# Sheet1.net
KiCad netlist of a schematic drawn in Altium Designer
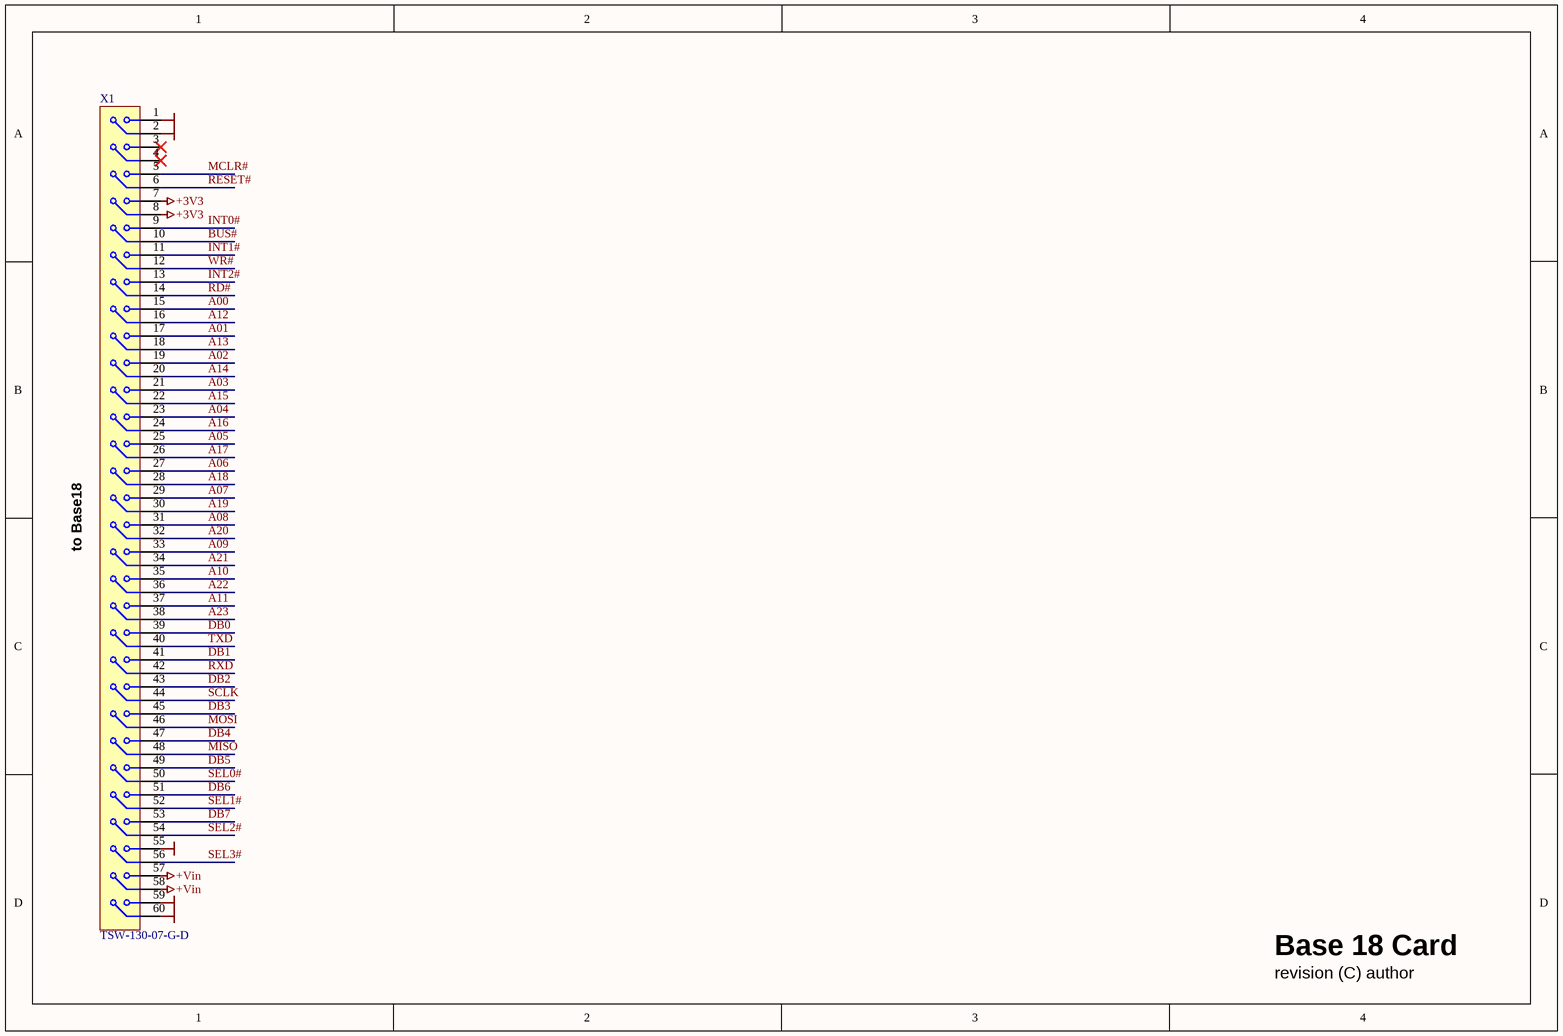
[diagram p0: Sheet1.SchDoc]

(export (version "E")
  (design (tool "Eeschema 10.0.6"))
  (components
    (comp (ref "X1")
      (value "TSW-130-07-G-D")
      (footprint "DIL60-M-EDGE")
      (description "Dual row, 60-way connector")
      (libsource (lib "Connectors") (part "Connector 2x30"))
    )
  )
  (nets
    (net (code "1") (name "+3V3") (class "Default")
      (node (ref "X1") (pin "7") (pinfunction "7_7") (pintype "passive"))
      (node (ref "X1") (pin "8") (pinfunction "8_8") (pintype "passive"))
    )
    (net (code "2") (name "+Vin") (class "Default")
      (node (ref "X1") (pin "57") (pinfunction "57_57") (pintype "passive"))
      (node (ref "X1") (pin "58") (pinfunction "58_58") (pintype "passive"))
    )
    (net (code "3") (name "/A00") (class "Default")
      (node (ref "X1") (pin "15") (pinfunction "15_15") (pintype "passive"))
    )
    (net (code "4") (name "/A01") (class "Default")
      (node (ref "X1") (pin "17") (pinfunction "17_17") (pintype "passive"))
    )
    (net (code "5") (name "/A02") (class "Default")
      (node (ref "X1") (pin "19") (pinfunction "19_19") (pintype "passive"))
    )
    (net (code "6") (name "/A03") (class "Default")
      (node (ref "X1") (pin "21") (pinfunction "21_21") (pintype "passive"))
    )
    (net (code "7") (name "/A04") (class "Default")
      (node (ref "X1") (pin "23") (pinfunction "23_23") (pintype "passive"))
    )
    (net (code "8") (name "/A05") (class "Default")
      (node (ref "X1") (pin "25") (pinfunction "25_25") (pintype "passive"))
    )
    (net (code "9") (name "/A06") (class "Default")
      (node (ref "X1") (pin "27") (pinfunction "27_27") (pintype "passive"))
    )
    (net (code "10") (name "/A07") (class "Default")
      (node (ref "X1") (pin "29") (pinfunction "29_29") (pintype "passive"))
    )
    (net (code "11") (name "/A08") (class "Default")
      (node (ref "X1") (pin "31") (pinfunction "31_31") (pintype "passive"))
    )
    (net (code "12") (name "/A09") (class "Default")
      (node (ref "X1") (pin "33") (pinfunction "33_33") (pintype "passive"))
    )
    (net (code "13") (name "/A10") (class "Default")
      (node (ref "X1") (pin "35") (pinfunction "35_35") (pintype "passive"))
    )
    (net (code "14") (name "/A11") (class "Default")
      (node (ref "X1") (pin "37") (pinfunction "37_37") (pintype "passive"))
    )
    (net (code "15") (name "/A12") (class "Default")
      (node (ref "X1") (pin "16") (pinfunction "16_16") (pintype "passive"))
    )
    (net (code "16") (name "/A13") (class "Default")
      (node (ref "X1") (pin "18") (pinfunction "18_18") (pintype "passive"))
    )
    (net (code "17") (name "/A14") (class "Default")
      (node (ref "X1") (pin "20") (pinfunction "20_20") (pintype "passive"))
    )
    (net (code "18") (name "/A15") (class "Default")
      (node (ref "X1") (pin "22") (pinfunction "22_22") (pintype "passive"))
    )
    (net (code "19") (name "/A16") (class "Default")
      (node (ref "X1") (pin "24") (pinfunction "24_24") (pintype "passive"))
    )
    (net (code "20") (name "/A17") (class "Default")
      (node (ref "X1") (pin "26") (pinfunction "26_26") (pintype "passive"))
    )
    (net (code "21") (name "/A18") (class "Default")
      (node (ref "X1") (pin "28") (pinfunction "28_28") (pintype "passive"))
    )
    (net (code "22") (name "/A19") (class "Default")
      (node (ref "X1") (pin "30") (pinfunction "30_30") (pintype "passive"))
    )
    (net (code "23") (name "/A20") (class "Default")
      (node (ref "X1") (pin "32") (pinfunction "32_32") (pintype "passive"))
    )
    (net (code "24") (name "/A21") (class "Default")
      (node (ref "X1") (pin "34") (pinfunction "34_34") (pintype "passive"))
    )
    (net (code "25") (name "/A22") (class "Default")
      (node (ref "X1") (pin "36") (pinfunction "36_36") (pintype "passive"))
    )
    (net (code "26") (name "/A23") (class "Default")
      (node (ref "X1") (pin "38") (pinfunction "38_38") (pintype "passive"))
    )
    (net (code "27") (name "/BUS#") (class "Default")
      (node (ref "X1") (pin "10") (pinfunction "10_10") (pintype "passive"))
    )
    (net (code "28") (name "/DB0") (class "Default")
      (node (ref "X1") (pin "39") (pinfunction "39_39") (pintype "passive"))
    )
    (net (code "29") (name "/DB1") (class "Default")
      (node (ref "X1") (pin "41") (pinfunction "41_41") (pintype "passive"))
    )
    (net (code "30") (name "/DB2") (class "Default")
      (node (ref "X1") (pin "43") (pinfunction "43_43") (pintype "passive"))
    )
    (net (code "31") (name "/DB3") (class "Default")
      (node (ref "X1") (pin "45") (pinfunction "45_45") (pintype "passive"))
    )
    (net (code "32") (name "/DB4") (class "Default")
      (node (ref "X1") (pin "47") (pinfunction "47_47") (pintype "passive"))
    )
    (net (code "33") (name "/DB5") (class "Default")
      (node (ref "X1") (pin "49") (pinfunction "49_49") (pintype "passive"))
    )
    (net (code "34") (name "/DB6") (class "Default")
      (node (ref "X1") (pin "51") (pinfunction "51_51") (pintype "passive"))
    )
    (net (code "35") (name "/DB7") (class "Default")
      (node (ref "X1") (pin "53") (pinfunction "53_53") (pintype "passive"))
    )
    (net (code "36") (name "/INT0#") (class "Default")
      (node (ref "X1") (pin "9") (pinfunction "9_9") (pintype "passive"))
    )
    (net (code "37") (name "/INT1#") (class "Default")
      (node (ref "X1") (pin "11") (pinfunction "11_11") (pintype "passive"))
    )
    (net (code "38") (name "/INT2#") (class "Default")
      (node (ref "X1") (pin "13") (pinfunction "13_13") (pintype "passive"))
    )
    (net (code "39") (name "/MCLR#") (class "Default")
      (node (ref "X1") (pin "5") (pinfunction "5_5") (pintype "passive"))
    )
    (net (code "40") (name "/MISO") (class "Default")
      (node (ref "X1") (pin "48") (pinfunction "48_48") (pintype "passive"))
    )
    (net (code "41") (name "/MOSI") (class "Default")
      (node (ref "X1") (pin "46") (pinfunction "46_46") (pintype "passive"))
    )
    (net (code "42") (name "/RD#") (class "Default")
      (node (ref "X1") (pin "14") (pinfunction "14_14") (pintype "passive"))
    )
    (net (code "43") (name "/RESET#") (class "Default")
      (node (ref "X1") (pin "6") (pinfunction "6_6") (pintype "passive"))
    )
    (net (code "44") (name "/RXD") (class "Default")
      (node (ref "X1") (pin "42") (pinfunction "42_42") (pintype "passive"))
    )
    (net (code "45") (name "/SCLK") (class "Default")
      (node (ref "X1") (pin "44") (pinfunction "44_44") (pintype "passive"))
    )
    (net (code "46") (name "/SEL0#") (class "Default")
      (node (ref "X1") (pin "50") (pinfunction "50_50") (pintype "passive"))
    )
    (net (code "47") (name "/SEL1#") (class "Default")
      (node (ref "X1") (pin "52") (pinfunction "52_52") (pintype "passive"))
    )
    (net (code "48") (name "/SEL2#") (class "Default")
      (node (ref "X1") (pin "54") (pinfunction "54_54") (pintype "passive"))
    )
    (net (code "49") (name "/SEL3#") (class "Default")
      (node (ref "X1") (pin "56") (pinfunction "56_56") (pintype "passive"))
    )
    (net (code "50") (name "/TXD") (class "Default")
      (node (ref "X1") (pin "40") (pinfunction "40_40") (pintype "passive"))
    )
    (net (code "51") (name "/WR#") (class "Default")
      (node (ref "X1") (pin "12") (pinfunction "12_12") (pintype "passive"))
    )
    (net (code "52") (name "GND") (class "Default")
      (node (ref "X1") (pin "1") (pinfunction "1_1") (pintype "passive"))
      (node (ref "X1") (pin "2") (pinfunction "2_2") (pintype "passive"))
      (node (ref "X1") (pin "55") (pinfunction "55_55") (pintype "passive"))
      (node (ref "X1") (pin "59") (pinfunction "59_59") (pintype "passive"))
      (node (ref "X1") (pin "60") (pinfunction "60_60") (pintype "passive"))
    )
    (net (code "53") (name "unconnected-(X1-Pad3)") (class "Default")
      (node (ref "X1") (pin "3") (pinfunction "3_3") (pintype "passive+no_connect"))
    )
    (net (code "54") (name "unconnected-(X1-Pad4)") (class "Default")
      (node (ref "X1") (pin "4") (pinfunction "4_4") (pintype "passive+no_connect"))
    )
  )
)
